# SC16IS740v4.net
KiCad netlist of a schematic drawn in EAGLE
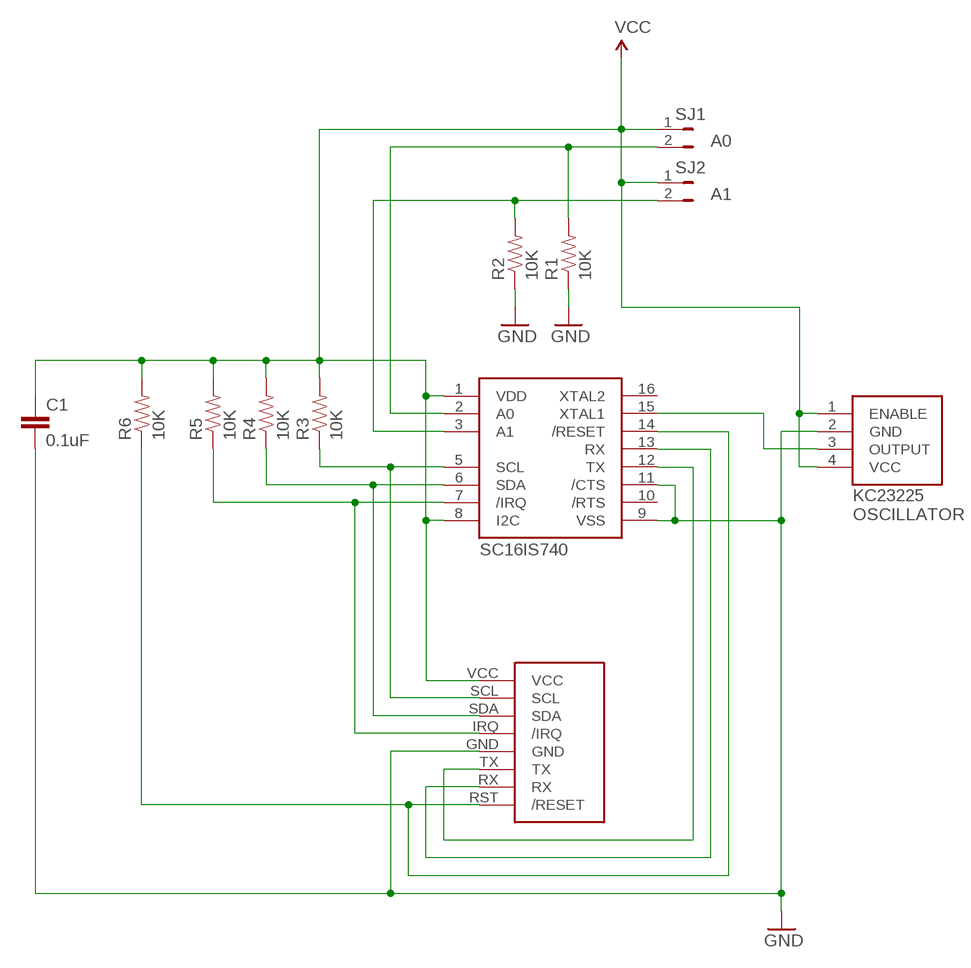
[diagram p0: schematic, sheet 1]

(export (version "E")
  (design (tool "Eeschema 10.0.6"))
  (components
    (comp (ref "C1")
      (value "0.1uF")
      (footprint "eagle-import:0603-CAP")
      (libsource (lib "eagle-import") (part "0.1UF-25V-5%(0603)"))
    )
    (comp (ref "R1")
      (value "10K")
      (footprint "eagle-import:0603-RES")
      (libsource (lib "eagle-import") (part "10KOHM-1/10W-1%(0603)0603"))
    )
    (comp (ref "R2")
      (value "10K")
      (footprint "eagle-import:0603-RES")
      (libsource (lib "eagle-import") (part "10KOHM-1/10W-1%(0603)0603"))
    )
    (comp (ref "R3")
      (value "10K")
      (footprint "eagle-import:0603-RES")
      (libsource (lib "eagle-import") (part "10KOHM-1/10W-1%(0603)0603"))
    )
    (comp (ref "R4")
      (value "10K")
      (footprint "eagle-import:0603-RES")
      (libsource (lib "eagle-import") (part "10KOHM-1/10W-1%(0603)0603"))
    )
    (comp (ref "R5")
      (value "10K")
      (footprint "eagle-import:0603-RES")
      (libsource (lib "eagle-import") (part "10KOHM-1/10W-1%(0603)0603"))
    )
    (comp (ref "R6")
      (value "10K")
      (footprint "eagle-import:0603-RES")
      (libsource (lib "eagle-import") (part "10KOHM-1/10W-1%(0603)0603"))
    )
    (comp (ref "SJ1")
      (value "JUMPER-PTH-2-NO")
      (footprint "eagle-import:PTH-JUMPER-2-NO_NO_SILK")
      (libsource (lib "eagle-import") (part "JUMPER-PTH-2-NO"))
    )
    (comp (ref "SJ2")
      (value "JUMPER-PTH-2-NO")
      (footprint "eagle-import:PTH-JUMPER-2-NO_NO_SILK")
      (libsource (lib "eagle-import") (part "JUMPER-PTH-2-NO"))
    )
    (comp (ref "U$1")
      (value "SC16IS740")
      (footprint "eagle-import:SC16IS740")
      (libsource (lib "eagle-import") (part "SC16IS740"))
    )
    (comp (ref "U$2")
      (value "HEADER-SC16IS740-NOFLOW")
      (footprint "eagle-import:HEADER-SC16IS740-NOFLOW")
      (libsource (lib "eagle-import") (part "HEADER-SC16IS740-NOFLOW"))
    )
    (comp (ref "U$3")
      (value "OSC-KC3225K")
      (footprint "eagle-import:OSC-KC3225K")
      (libsource (lib "eagle-import") (part "OSC-KC3225K"))
    )
  )
  (nets
    (net (code "1") (name "/A0") (class "Default")
      (node (ref "R1") (pin "2") (pinfunction "2_2") (pintype "passive"))
      (node (ref "SJ1") (pin "2") (pinfunction "2_2") (pintype "passive"))
      (node (ref "U$1") (pin "2") (pinfunction "A0_2") (pintype "input"))
    )
    (net (code "2") (name "/A1") (class "Default")
      (node (ref "R2") (pin "2") (pinfunction "2_2") (pintype "passive"))
      (node (ref "SJ2") (pin "2") (pinfunction "2_2") (pintype "passive"))
      (node (ref "U$1") (pin "3") (pinfunction "A1_3") (pintype "input"))
    )
    (net (code "3") (name "GND") (class "Default")
      (node (ref "C1") (pin "2") (pinfunction "2_2") (pintype "passive"))
      (node (ref "R1") (pin "1") (pinfunction "1_1") (pintype "passive"))
      (node (ref "R2") (pin "1") (pinfunction "1_1") (pintype "passive"))
      (node (ref "U$1") (pin "11") (pinfunction "/CTS_11") (pintype "input"))
      (node (ref "U$1") (pin "9") (pinfunction "VSS_9") (pintype "power_in"))
      (node (ref "U$2") (pin "GND") (pinfunction "GND_GND") (pintype "power_in"))
      (node (ref "U$3") (pin "2") (pinfunction "GND_2") (pintype "power_in"))
    )
    (net (code "4") (name "Net-(U$1-RX)") (class "Default")
      (node (ref "U$1") (pin "13") (pinfunction "RX_13") (pintype "input"))
      (node (ref "U$2") (pin "RX") (pinfunction "RX_RX") (pintype "passive"))
    )
    (net (code "5") (name "Net-(U$1-SCL)") (class "Default")
      (node (ref "R3") (pin "1") (pinfunction "1_1") (pintype "passive"))
      (node (ref "U$1") (pin "5") (pinfunction "SCL_5") (pintype "bidirectional"))
      (node (ref "U$2") (pin "SCL") (pinfunction "SCL_SCL") (pintype "passive"))
    )
    (net (code "6") (name "Net-(U$1-SDA)") (class "Default")
      (node (ref "R4") (pin "1") (pinfunction "1_1") (pintype "passive"))
      (node (ref "U$1") (pin "6") (pinfunction "SDA_6") (pintype "bidirectional"))
      (node (ref "U$2") (pin "SDA") (pinfunction "SDA_SDA") (pintype "passive"))
    )
    (net (code "7") (name "Net-(U$1-TX)") (class "Default")
      (node (ref "U$1") (pin "12") (pinfunction "TX_12") (pintype "output"))
      (node (ref "U$2") (pin "TX") (pinfunction "TX_TX") (pintype "passive"))
    )
    (net (code "8") (name "Net-(U$1-XTAL1)") (class "Default")
      (node (ref "U$1") (pin "15") (pinfunction "XTAL1_15") (pintype "input"))
      (node (ref "U$3") (pin "3") (pinfunction "OUTPUT_3") (pintype "output"))
    )
    (net (code "9") (name "Net-(U$1-{slash}IRQ)") (class "Default")
      (node (ref "R5") (pin "1") (pinfunction "1_1") (pintype "passive"))
      (node (ref "U$1") (pin "7") (pinfunction "/IRQ_7") (pintype "output"))
      (node (ref "U$2") (pin "IRQ") (pinfunction "/IRQ_IRQ") (pintype "passive"))
    )
    (net (code "10") (name "Net-(U$1-{slash}RESET)") (class "Default")
      (node (ref "R6") (pin "1") (pinfunction "1_1") (pintype "passive"))
      (node (ref "U$1") (pin "14") (pinfunction "/RESET_14") (pintype "input"))
      (node (ref "U$2") (pin "RST") (pinfunction "/RESET_RST") (pintype "passive"))
    )
    (net (code "11") (name "VCC") (class "Default")
      (node (ref "C1") (pin "1") (pinfunction "1_1") (pintype "passive"))
      (node (ref "R3") (pin "2") (pinfunction "2_2") (pintype "passive"))
      (node (ref "R4") (pin "2") (pinfunction "2_2") (pintype "passive"))
      (node (ref "R5") (pin "2") (pinfunction "2_2") (pintype "passive"))
      (node (ref "R6") (pin "2") (pinfunction "2_2") (pintype "passive"))
      (node (ref "SJ1") (pin "1") (pinfunction "1_1") (pintype "passive"))
      (node (ref "SJ2") (pin "1") (pinfunction "1_1") (pintype "passive"))
      (node (ref "U$1") (pin "1") (pinfunction "VDD_1") (pintype "power_in"))
      (node (ref "U$1") (pin "8") (pinfunction "I2C_8") (pintype "input"))
      (node (ref "U$2") (pin "VCC") (pinfunction "VCC_VCC") (pintype "power_in"))
      (node (ref "U$3") (pin "1") (pinfunction "ENABLE_1") (pintype "input"))
      (node (ref "U$3") (pin "4") (pinfunction "VCC_4") (pintype "power_in"))
    )
    (net (code "12") (name "unconnected-(U$1-XTAL2-Pad16)") (class "Default")
      (node (ref "U$1") (pin "16") (pinfunction "XTAL2_16") (pintype "bidirectional"))
    )
    (net (code "13") (name "unconnected-(U$1-{slash}RTS-Pad10)") (class "Default")
      (node (ref "U$1") (pin "10") (pinfunction "/RTS_10") (pintype "output"))
    )
  )
)
